# breakout-DS.net
KiCad netlist of a schematic drawn in EAGLE
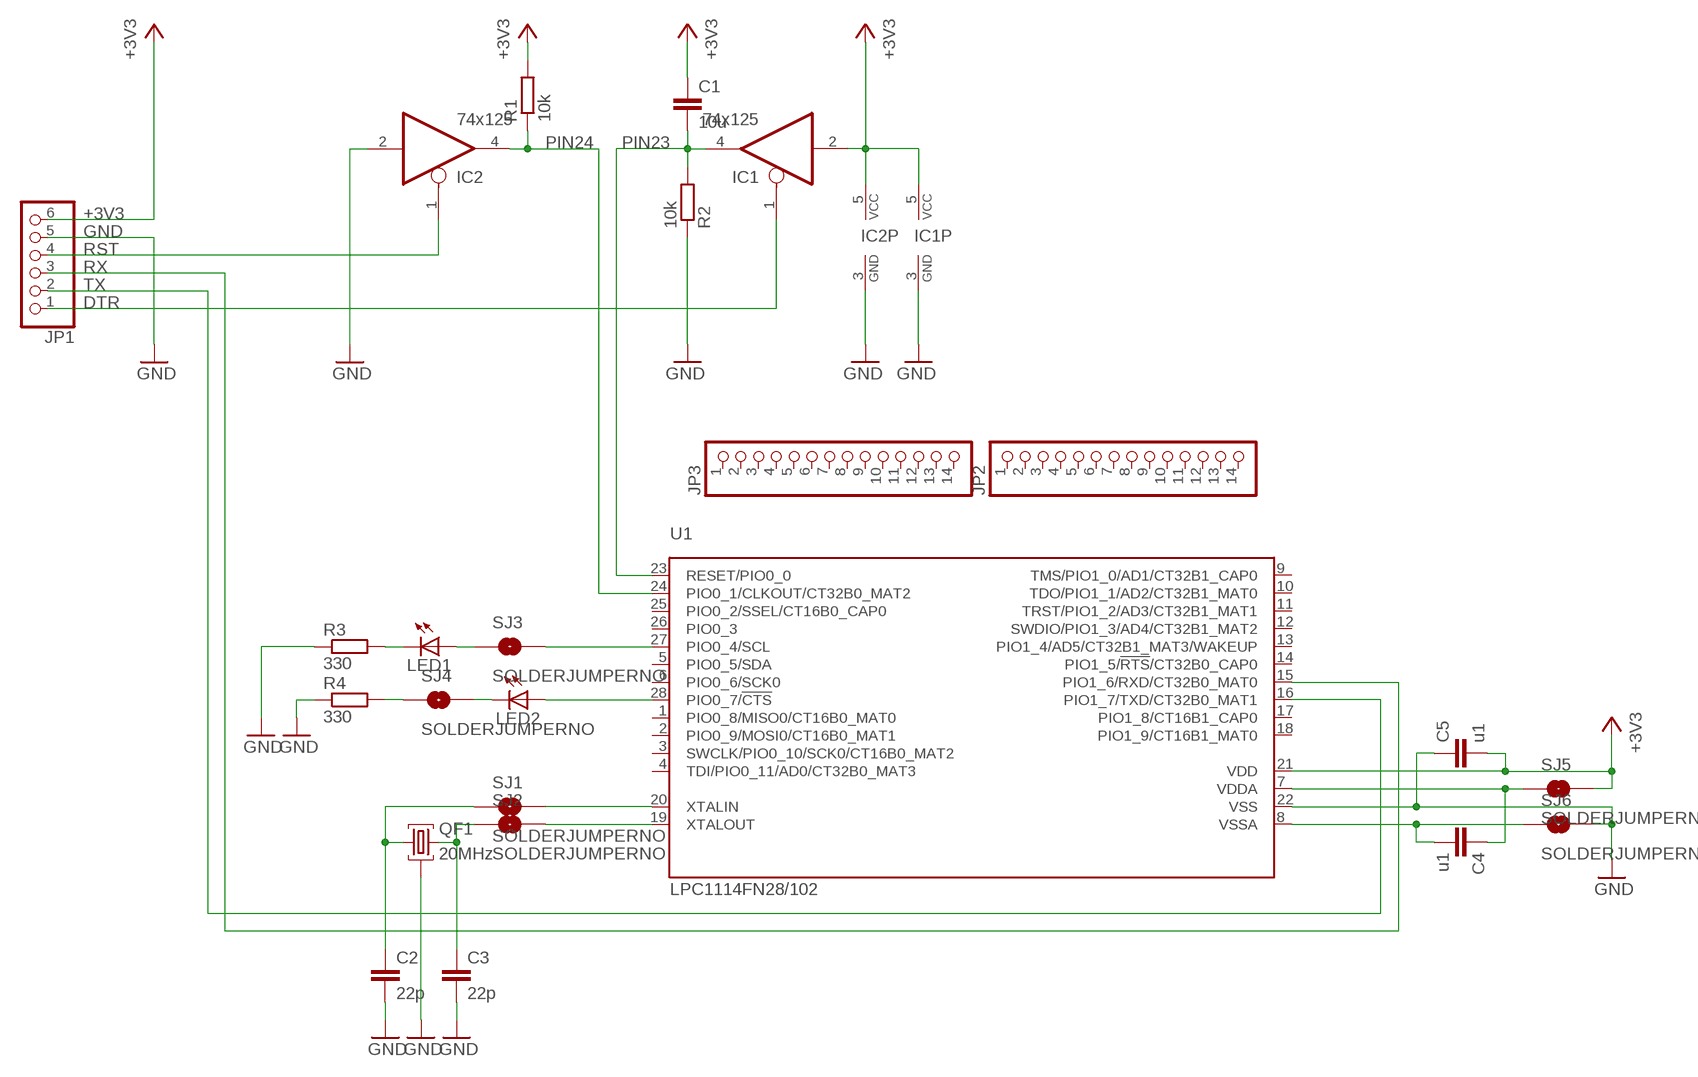
[diagram p0: schematic, sheet 1]

(export (version "E")
  (design (tool "Eeschema 10.0.6"))
  (components
    (comp (ref "C1")
      (value "10u")
      (footprint "eagle-import:C0805K")
      (libsource (lib "eagle-import") (part "C-EUC0805K"))
    )
    (comp (ref "C2")
      (value "22p")
      (footprint "eagle-import:C0805K")
      (libsource (lib "eagle-import") (part "C-EUC0805K"))
    )
    (comp (ref "C3")
      (value "22p")
      (footprint "eagle-import:C0805K")
      (libsource (lib "eagle-import") (part "C-EUC0805K"))
    )
    (comp (ref "C4")
      (value "u1")
      (footprint "eagle-import:C0805K")
      (libsource (lib "eagle-import") (part "C-EUC0805K"))
    )
    (comp (ref "C5")
      (value "u1")
      (footprint "eagle-import:C0805K")
      (libsource (lib "eagle-import") (part "C-EUC0805K"))
    )
    (comp (ref "IC1")
      (value "74x125")
      (footprint "eagle-import:SOT23-5")
      (libsource (lib "eagle-import") (part "741G125DBVAHC"))
    )
    (comp (ref "IC2")
      (value "74x125")
      (footprint "eagle-import:SOT23-5")
      (libsource (lib "eagle-import") (part "741G125DBVAHC"))
    )
    (comp (ref "JP1")
      (value "PINHD-1X6/90")
      (footprint "eagle-import:1X06_90")
      (libsource (lib "eagle-import") (part "PINHD-1X6/90"))
    )
    (comp (ref "JP2")
      (value "PINHD-1X14")
      (footprint "eagle-import:1X14")
      (libsource (lib "eagle-import") (part "PINHD-1X14"))
    )
    (comp (ref "JP3")
      (value "PINHD-1X14")
      (footprint "eagle-import:1X14")
      (libsource (lib "eagle-import") (part "PINHD-1X14"))
    )
    (comp (ref "LED1")
      (value "LEDLD260")
      (footprint "eagle-import:LD260")
      (libsource (lib "eagle-import") (part "LEDLD260"))
    )
    (comp (ref "LED2")
      (value "LEDLD260")
      (footprint "eagle-import:LD260")
      (libsource (lib "eagle-import") (part "LEDLD260"))
    )
    (comp (ref "QF1")
      (value "20MHz")
      (footprint "eagle-import:HC49U")
      (libsource (lib "eagle-import") (part "10MAHC49T7"))
    )
    (comp (ref "R1")
      (value "10k")
      (footprint "eagle-import:M0805")
      (libsource (lib "eagle-import") (part "R-EU_M0805"))
    )
    (comp (ref "R2")
      (value "10k")
      (footprint "eagle-import:M0805")
      (libsource (lib "eagle-import") (part "R-EU_M0805"))
    )
    (comp (ref "R3")
      (value "330")
      (footprint "eagle-import:M0805")
      (libsource (lib "eagle-import") (part "R-EU_M0805"))
    )
    (comp (ref "R4")
      (value "330")
      (footprint "eagle-import:M0805")
      (libsource (lib "eagle-import") (part "R-EU_M0805"))
    )
    (comp (ref "SJ1")
      (value "SOLDERJUMPERNO")
      (footprint "eagle-import:SJ_2S-NO")
      (libsource (lib "eagle-import") (part "SOLDERJUMPERNO"))
    )
    (comp (ref "SJ2")
      (value "SOLDERJUMPERNO")
      (footprint "eagle-import:SJ_2S-NO")
      (libsource (lib "eagle-import") (part "SOLDERJUMPERNO"))
    )
    (comp (ref "SJ3")
      (value "SOLDERJUMPERNO")
      (footprint "eagle-import:SJ_2S-NO")
      (libsource (lib "eagle-import") (part "SOLDERJUMPERNO"))
    )
    (comp (ref "SJ4")
      (value "SOLDERJUMPERNO")
      (footprint "eagle-import:SJ_2S-NO")
      (libsource (lib "eagle-import") (part "SOLDERJUMPERNO"))
    )
    (comp (ref "SJ5")
      (value "SOLDERJUMPERNO")
      (footprint "eagle-import:SJ_2S-NO")
      (libsource (lib "eagle-import") (part "SOLDERJUMPERNO"))
    )
    (comp (ref "SJ6")
      (value "SOLDERJUMPERNO")
      (footprint "eagle-import:SJ_2S-NO")
      (libsource (lib "eagle-import") (part "SOLDERJUMPERNO"))
    )
    (comp (ref "U1")
      (value "LPC1114FN28/102")
      (footprint "eagle-import:SOT117")
      (libsource (lib "eagle-import") (part "LPC1114FN28/102"))
    )
  )
  (nets
    (net (code "1") (name "+3V3") (class "Default")
      (node (ref "C1") (pin "1") (pinfunction "1_1") (pintype "passive"))
      (node (ref "C5") (pin "2") (pinfunction "2_2") (pintype "passive"))
      (node (ref "IC1") (pin "2") (pinfunction "I_2") (pintype "input"))
      (node (ref "IC1") (pin "5") (pinfunction "VCC_5") (pintype "power_in"))
      (node (ref "IC2") (pin "5") (pinfunction "VCC_5") (pintype "power_in"))
      (node (ref "JP1") (pin "6") (pinfunction "6_6") (pintype "passive"))
      (node (ref "R1") (pin "2") (pinfunction "2_2") (pintype "passive"))
      (node (ref "SJ5") (pin "2") (pinfunction "2_2") (pintype "passive"))
      (node (ref "U1") (pin "21") (pinfunction "VDD_21") (pintype "power_in"))
    )
    (net (code "2") (name "/DTR") (class "Default")
      (node (ref "IC1") (pin "1") (pinfunction "OE_1") (pintype "input"))
      (node (ref "JP1") (pin "1") (pinfunction "1_1") (pintype "passive"))
    )
    (net (code "3") (name "/PIN23") (class "Default")
      (node (ref "C1") (pin "2") (pinfunction "2_2") (pintype "passive"))
      (node (ref "IC1") (pin "4") (pinfunction "O_4") (pintype "tri_state"))
      (node (ref "R2") (pin "2") (pinfunction "2_2") (pintype "passive"))
      (node (ref "U1") (pin "23") (pinfunction "RESET/PIO0_0_23") (pintype "bidirectional"))
    )
    (net (code "4") (name "/PIN24") (class "Default")
      (node (ref "IC2") (pin "4") (pinfunction "O_4") (pintype "tri_state"))
      (node (ref "R1") (pin "1") (pinfunction "1_1") (pintype "passive"))
      (node (ref "U1") (pin "24") (pinfunction "PIO0_1/CLKOUT/CT32B0_MAT2_24") (pintype "bidirectional"))
    )
    (net (code "5") (name "/RST") (class "Default")
      (node (ref "IC2") (pin "1") (pinfunction "OE_1") (pintype "input"))
      (node (ref "JP1") (pin "4") (pinfunction "4_4") (pintype "passive"))
    )
    (net (code "6") (name "/RX") (class "Default")
      (node (ref "JP1") (pin "3") (pinfunction "3_3") (pintype "passive"))
      (node (ref "U1") (pin "15") (pinfunction "PIO1_6/RXD/CT32B0_MAT0_15") (pintype "bidirectional"))
    )
    (net (code "7") (name "/TX") (class "Default")
      (node (ref "JP1") (pin "2") (pinfunction "2_2") (pintype "passive"))
      (node (ref "U1") (pin "16") (pinfunction "PIO1_7/TXD/CT32B0_MAT1_16") (pintype "bidirectional"))
    )
    (net (code "8") (name "GND") (class "Default")
      (node (ref "C2") (pin "2") (pinfunction "2_2") (pintype "passive"))
      (node (ref "C3") (pin "2") (pinfunction "2_2") (pintype "passive"))
      (node (ref "C5") (pin "1") (pinfunction "1_1") (pintype "passive"))
      (node (ref "IC1") (pin "3") (pinfunction "GND_3") (pintype "power_in"))
      (node (ref "IC2") (pin "2") (pinfunction "I_2") (pintype "input"))
      (node (ref "IC2") (pin "3") (pinfunction "GND_3") (pintype "power_in"))
      (node (ref "JP1") (pin "5") (pinfunction "5_5") (pintype "passive"))
      (node (ref "QF1") (pin "2") (pinfunction "2_2") (pintype "passive"))
      (node (ref "R2") (pin "1") (pinfunction "1_1") (pintype "passive"))
      (node (ref "R3") (pin "1") (pinfunction "1_1") (pintype "passive"))
      (node (ref "R4") (pin "1") (pinfunction "1_1") (pintype "passive"))
      (node (ref "SJ6") (pin "2") (pinfunction "2_2") (pintype "passive"))
      (node (ref "U1") (pin "22") (pinfunction "VSS_22") (pintype "power_in"))
    )
    (net (code "9") (name "Net-(C2-Pad1)") (class "Default")
      (node (ref "C2") (pin "1") (pinfunction "1_1") (pintype "passive"))
      (node (ref "QF1") (pin "1") (pinfunction "1_1") (pintype "passive"))
      (node (ref "SJ1") (pin "1") (pinfunction "1_1") (pintype "passive"))
    )
    (net (code "10") (name "Net-(C3-Pad1)") (class "Default")
      (node (ref "C3") (pin "1") (pinfunction "1_1") (pintype "passive"))
      (node (ref "QF1") (pin "3") (pinfunction "3_3") (pintype "passive"))
      (node (ref "SJ2") (pin "1") (pinfunction "1_1") (pintype "passive"))
    )
    (net (code "11") (name "Net-(LED1-C)") (class "Default")
      (node (ref "LED1") (pin "K") (pinfunction "C_K") (pintype "passive"))
      (node (ref "R3") (pin "2") (pinfunction "2_2") (pintype "passive"))
    )
    (net (code "12") (name "Net-(LED1-PadA)") (class "Default")
      (node (ref "LED1") (pin "A") (pinfunction "A_A") (pintype "passive"))
      (node (ref "SJ3") (pin "1") (pinfunction "1_1") (pintype "passive"))
    )
    (net (code "13") (name "Net-(LED2-C)") (class "Default")
      (node (ref "LED2") (pin "K") (pinfunction "C_K") (pintype "passive"))
      (node (ref "SJ4") (pin "2") (pinfunction "2_2") (pintype "passive"))
    )
    (net (code "14") (name "Net-(R4-Pad2)") (class "Default")
      (node (ref "R4") (pin "2") (pinfunction "2_2") (pintype "passive"))
      (node (ref "SJ4") (pin "1") (pinfunction "1_1") (pintype "passive"))
    )
    (net (code "15") (name "Net-(U1-PIO0_4{slash}SCL)") (class "Default")
      (node (ref "SJ3") (pin "2") (pinfunction "2_2") (pintype "passive"))
      (node (ref "U1") (pin "27") (pinfunction "PIO0_4/SCL_27") (pintype "bidirectional"))
    )
    (net (code "16") (name "Net-(U1-PIO0_7{slash}~{CTS})") (class "Default")
      (node (ref "LED2") (pin "A") (pinfunction "A_A") (pintype "passive"))
      (node (ref "U1") (pin "28") (pinfunction "PIO0_7/~{CTS}_28") (pintype "bidirectional"))
    )
    (net (code "17") (name "Net-(U1-VDDA)") (class "Default")
      (node (ref "C4") (pin "1") (pinfunction "1_1") (pintype "passive"))
      (node (ref "SJ5") (pin "1") (pinfunction "1_1") (pintype "passive"))
      (node (ref "U1") (pin "7") (pinfunction "VDDA_7") (pintype "power_in"))
    )
    (net (code "18") (name "Net-(U1-VSSA)") (class "Default")
      (node (ref "C4") (pin "2") (pinfunction "2_2") (pintype "passive"))
      (node (ref "SJ6") (pin "1") (pinfunction "1_1") (pintype "passive"))
      (node (ref "U1") (pin "8") (pinfunction "VSSA_8") (pintype "power_in"))
    )
    (net (code "19") (name "Net-(U1-XTALIN)") (class "Default")
      (node (ref "SJ1") (pin "2") (pinfunction "2_2") (pintype "passive"))
      (node (ref "U1") (pin "20") (pinfunction "XTALIN_20") (pintype "input"))
    )
    (net (code "20") (name "Net-(U1-XTALOUT)") (class "Default")
      (node (ref "SJ2") (pin "2") (pinfunction "2_2") (pintype "passive"))
      (node (ref "U1") (pin "19") (pinfunction "XTALOUT_19") (pintype "output"))
    )
    (net (code "21") (name "unconnected-(JP2-Pad1)") (class "Default")
      (node (ref "JP2") (pin "1") (pinfunction "1_1") (pintype "passive"))
    )
    (net (code "22") (name "unconnected-(JP2-Pad2)") (class "Default")
      (node (ref "JP2") (pin "2") (pinfunction "2_2") (pintype "passive"))
    )
    (net (code "23") (name "unconnected-(JP2-Pad3)") (class "Default")
      (node (ref "JP2") (pin "3") (pinfunction "3_3") (pintype "passive"))
    )
    (net (code "24") (name "unconnected-(JP2-Pad4)") (class "Default")
      (node (ref "JP2") (pin "4") (pinfunction "4_4") (pintype "passive"))
    )
    (net (code "25") (name "unconnected-(JP2-Pad5)") (class "Default")
      (node (ref "JP2") (pin "5") (pinfunction "5_5") (pintype "passive"))
    )
    (net (code "26") (name "unconnected-(JP2-Pad6)") (class "Default")
      (node (ref "JP2") (pin "6") (pinfunction "6_6") (pintype "passive"))
    )
    (net (code "27") (name "unconnected-(JP2-Pad7)") (class "Default")
      (node (ref "JP2") (pin "7") (pinfunction "7_7") (pintype "passive"))
    )
    (net (code "28") (name "unconnected-(JP2-Pad8)") (class "Default")
      (node (ref "JP2") (pin "8") (pinfunction "8_8") (pintype "passive"))
    )
    (net (code "29") (name "unconnected-(JP2-Pad9)") (class "Default")
      (node (ref "JP2") (pin "9") (pinfunction "9_9") (pintype "passive"))
    )
    (net (code "30") (name "unconnected-(JP2-Pad10)") (class "Default")
      (node (ref "JP2") (pin "10") (pinfunction "10_10") (pintype "passive"))
    )
    (net (code "31") (name "unconnected-(JP2-Pad11)") (class "Default")
      (node (ref "JP2") (pin "11") (pinfunction "11_11") (pintype "passive"))
    )
    (net (code "32") (name "unconnected-(JP2-Pad12)") (class "Default")
      (node (ref "JP2") (pin "12") (pinfunction "12_12") (pintype "passive"))
    )
    (net (code "33") (name "unconnected-(JP2-Pad13)") (class "Default")
      (node (ref "JP2") (pin "13") (pinfunction "13_13") (pintype "passive"))
    )
    (net (code "34") (name "unconnected-(JP2-Pad14)") (class "Default")
      (node (ref "JP2") (pin "14") (pinfunction "14_14") (pintype "passive"))
    )
    (net (code "35") (name "unconnected-(JP3-Pad1)") (class "Default")
      (node (ref "JP3") (pin "1") (pinfunction "1_1") (pintype "passive"))
    )
    (net (code "36") (name "unconnected-(JP3-Pad2)") (class "Default")
      (node (ref "JP3") (pin "2") (pinfunction "2_2") (pintype "passive"))
    )
    (net (code "37") (name "unconnected-(JP3-Pad3)") (class "Default")
      (node (ref "JP3") (pin "3") (pinfunction "3_3") (pintype "passive"))
    )
    (net (code "38") (name "unconnected-(JP3-Pad4)") (class "Default")
      (node (ref "JP3") (pin "4") (pinfunction "4_4") (pintype "passive"))
    )
    (net (code "39") (name "unconnected-(JP3-Pad5)") (class "Default")
      (node (ref "JP3") (pin "5") (pinfunction "5_5") (pintype "passive"))
    )
    (net (code "40") (name "unconnected-(JP3-Pad6)") (class "Default")
      (node (ref "JP3") (pin "6") (pinfunction "6_6") (pintype "passive"))
    )
    (net (code "41") (name "unconnected-(JP3-Pad7)") (class "Default")
      (node (ref "JP3") (pin "7") (pinfunction "7_7") (pintype "passive"))
    )
    (net (code "42") (name "unconnected-(JP3-Pad8)") (class "Default")
      (node (ref "JP3") (pin "8") (pinfunction "8_8") (pintype "passive"))
    )
    (net (code "43") (name "unconnected-(JP3-Pad9)") (class "Default")
      (node (ref "JP3") (pin "9") (pinfunction "9_9") (pintype "passive"))
    )
    (net (code "44") (name "unconnected-(JP3-Pad10)") (class "Default")
      (node (ref "JP3") (pin "10") (pinfunction "10_10") (pintype "passive"))
    )
    (net (code "45") (name "unconnected-(JP3-Pad11)") (class "Default")
      (node (ref "JP3") (pin "11") (pinfunction "11_11") (pintype "passive"))
    )
    (net (code "46") (name "unconnected-(JP3-Pad12)") (class "Default")
      (node (ref "JP3") (pin "12") (pinfunction "12_12") (pintype "passive"))
    )
    (net (code "47") (name "unconnected-(JP3-Pad13)") (class "Default")
      (node (ref "JP3") (pin "13") (pinfunction "13_13") (pintype "passive"))
    )
    (net (code "48") (name "unconnected-(JP3-Pad14)") (class "Default")
      (node (ref "JP3") (pin "14") (pinfunction "14_14") (pintype "passive"))
    )
    (net (code "49") (name "unconnected-(U1-PIO0_2{slash}SSEL{slash}CT16B0_CAP0-Pad25)") (class "Default")
      (node (ref "U1") (pin "25") (pinfunction "PIO0_2/SSEL/CT16B0_CAP0_25") (pintype "bidirectional"))
    )
    (net (code "50") (name "unconnected-(U1-PIO0_3-Pad26)") (class "Default")
      (node (ref "U1") (pin "26") (pinfunction "PIO0_3_26") (pintype "bidirectional"))
    )
    (net (code "51") (name "unconnected-(U1-PIO0_5{slash}SDA-Pad5)") (class "Default")
      (node (ref "U1") (pin "5") (pinfunction "PIO0_5/SDA_5") (pintype "bidirectional"))
    )
    (net (code "52") (name "unconnected-(U1-PIO0_6{slash}SCK0-Pad6)") (class "Default")
      (node (ref "U1") (pin "6") (pinfunction "PIO0_6/SCK0_6") (pintype "bidirectional"))
    )
    (net (code "53") (name "unconnected-(U1-PIO0_8{slash}MISO0{slash}CT16B0_MAT0-Pad1)") (class "Default")
      (node (ref "U1") (pin "1") (pinfunction "PIO0_8/MISO0/CT16B0_MAT0_1") (pintype "bidirectional"))
    )
    (net (code "54") (name "unconnected-(U1-PIO0_9{slash}MOSI0{slash}CT16B0_MAT1-Pad2)") (class "Default")
      (node (ref "U1") (pin "2") (pinfunction "PIO0_9/MOSI0/CT16B0_MAT1_2") (pintype "bidirectional"))
    )
    (net (code "55") (name "unconnected-(U1-PIO1_4{slash}AD5{slash}CT32B1_MAT3{slash}WAKEUP-Pad13)") (class "Default")
      (node (ref "U1") (pin "13") (pinfunction "PIO1_4/AD5/CT32B1_MAT3/WAKEUP_13") (pintype "bidirectional"))
    )
    (net (code "56") (name "unconnected-(U1-PIO1_5{slash}~{RTS}{slash}CT32B0_CAP0-Pad14)") (class "Default")
      (node (ref "U1") (pin "14") (pinfunction "PIO1_5/~{RTS}/CT32B0_CAP0_14") (pintype "bidirectional"))
    )
    (net (code "57") (name "unconnected-(U1-PIO1_8{slash}CT16B1_CAP0-Pad17)") (class "Default")
      (node (ref "U1") (pin "17") (pinfunction "PIO1_8/CT16B1_CAP0_17") (pintype "bidirectional"))
    )
    (net (code "58") (name "unconnected-(U1-PIO1_9{slash}CT16B1_MAT0-Pad18)") (class "Default")
      (node (ref "U1") (pin "18") (pinfunction "PIO1_9/CT16B1_MAT0_18") (pintype "bidirectional"))
    )
    (net (code "59") (name "unconnected-(U1-SWCLK{slash}PIO0_10{slash}SCK0{slash}CT16B0_MAT2-Pad3)") (class "Default")
      (node (ref "U1") (pin "3") (pinfunction "SWCLK/PIO0_10/SCK0/CT16B0_MAT2_3") (pintype "bidirectional"))
    )
    (net (code "60") (name "unconnected-(U1-SWDIO{slash}PIO1_3{slash}AD4{slash}CT32B1_MAT2-Pad12)") (class "Default")
      (node (ref "U1") (pin "12") (pinfunction "SWDIO/PIO1_3/AD4/CT32B1_MAT2_12") (pintype "bidirectional"))
    )
    (net (code "61") (name "unconnected-(U1-TDI{slash}PIO0_11{slash}AD0{slash}CT32B0_MAT3-Pad4)") (class "Default")
      (node (ref "U1") (pin "4") (pinfunction "TDI/PIO0_11/AD0/CT32B0_MAT3_4") (pintype "bidirectional"))
    )
    (net (code "62") (name "unconnected-(U1-TDO{slash}PIO1_1{slash}AD2{slash}CT32B1_MAT0-Pad10)") (class "Default")
      (node (ref "U1") (pin "10") (pinfunction "TDO/PIO1_1/AD2/CT32B1_MAT0_10") (pintype "bidirectional"))
    )
    (net (code "63") (name "unconnected-(U1-TMS{slash}PIO1_0{slash}AD1{slash}CT32B1_CAP0-Pad9)") (class "Default")
      (node (ref "U1") (pin "9") (pinfunction "TMS/PIO1_0/AD1/CT32B1_CAP0_9") (pintype "bidirectional"))
    )
    (net (code "64") (name "unconnected-(U1-TRST{slash}PIO1_2{slash}AD3{slash}CT32B1_MAT1-Pad11)") (class "Default")
      (node (ref "U1") (pin "11") (pinfunction "TRST/PIO1_2/AD3/CT32B1_MAT1_11") (pintype "bidirectional"))
    )
  )
)
